# Sheet1_-.net
KiCad netlist of a schematic drawn in Altium Designer
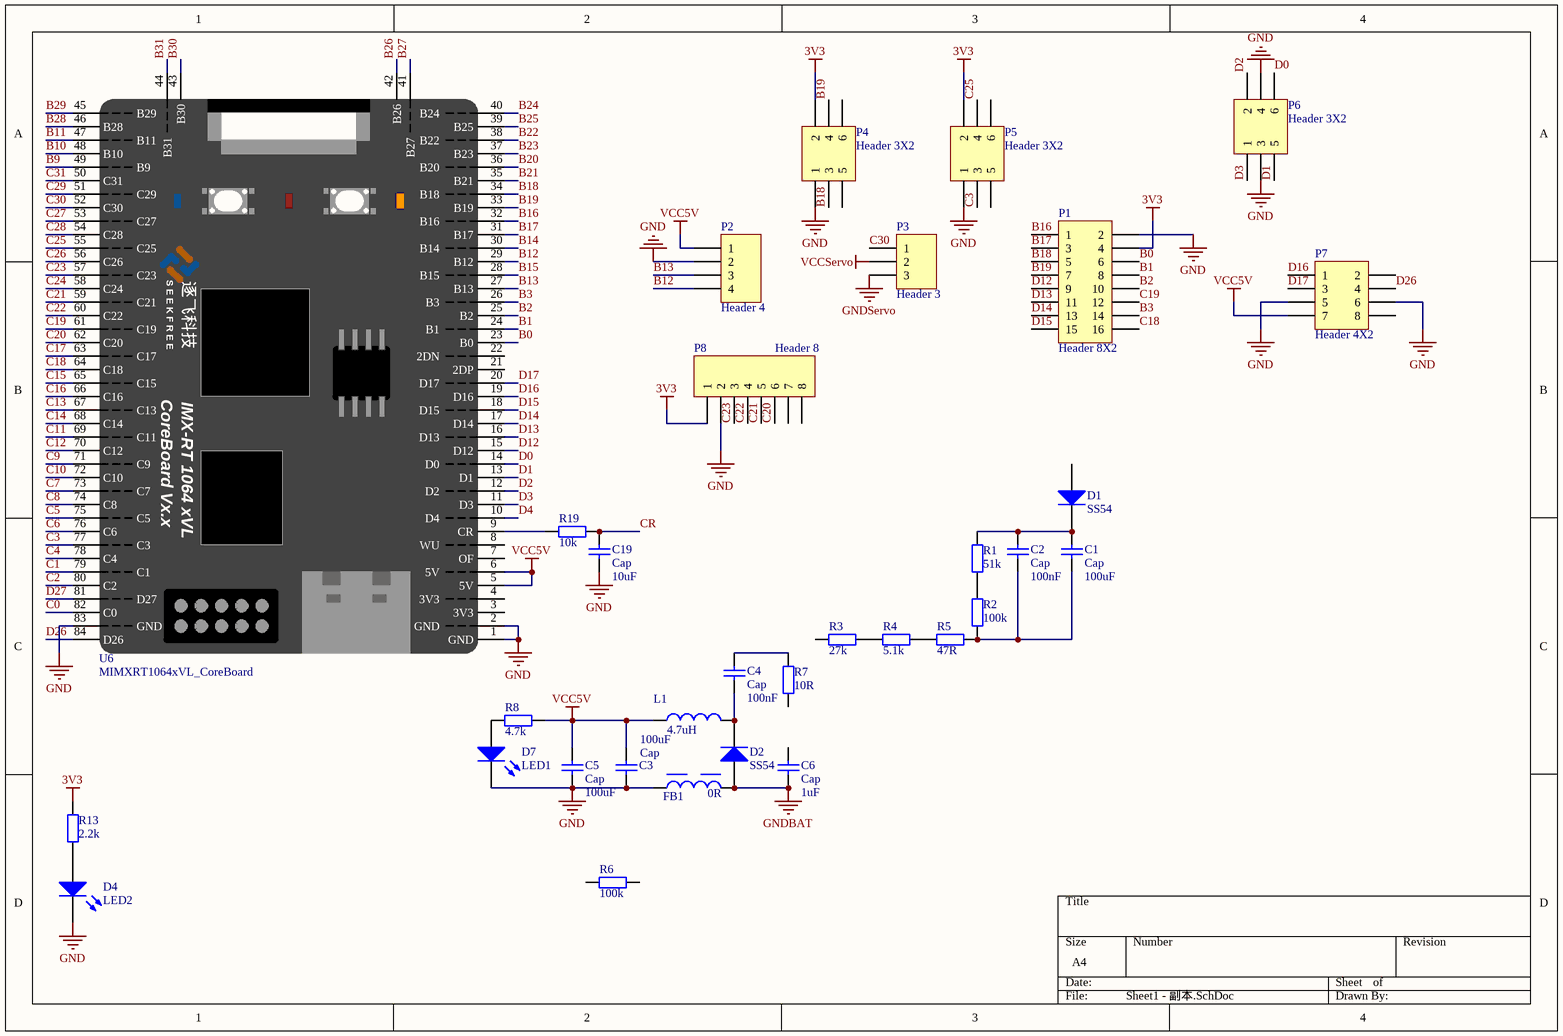
[diagram p0: Sheet1 - 副本.SchDoc]

(export (version "E")
  (design (tool "Eeschema 10.0.6"))
  (components
    (comp (ref "C1")
      (value "Cap")
      (footprint "0603C")
      (description "Capacitor")
      (fields (field (name "ALTIUM_VALUE") "100uF") (field (name "PUBLISHER") "Altium Limited"))
      (libsource (lib "Schlib1") (part "Cap"))
    )
    (comp (ref "C2")
      (value "Cap")
      (footprint "0603C")
      (description "Capacitor")
      (fields (field (name "ALTIUM_VALUE") "100nF") (field (name "PUBLISHER") "Altium Limited"))
      (libsource (lib "Schlib1") (part "Cap"))
    )
    (comp (ref "C3")
      (value "Cap")
      (footprint "0603C")
      (description "Capacitor")
      (fields (field (name "ALTIUM_VALUE") "100uF") (field (name "PUBLISHER") "Altium Limited"))
      (libsource (lib "Schlib1") (part "Cap"))
    )
    (comp (ref "C4")
      (value "Cap")
      (footprint "0603C")
      (description "Capacitor")
      (fields (field (name "ALTIUM_VALUE") "100nF") (field (name "PUBLISHER") "Altium Limited"))
      (libsource (lib "Schlib1") (part "Cap"))
    )
    (comp (ref "C5")
      (value "Cap")
      (footprint "0603C")
      (description "Capacitor")
      (fields (field (name "ALTIUM_VALUE") "100uF") (field (name "PUBLISHER") "Altium Limited"))
      (libsource (lib "Schlib1") (part "Cap"))
    )
    (comp (ref "C6")
      (value "Cap")
      (footprint "0603C")
      (description "Capacitor")
      (fields (field (name "ALTIUM_VALUE") "1uF") (field (name "PUBLISHER") "Altium Limited"))
      (libsource (lib "Schlib1") (part "Cap"))
    )
    (comp (ref "C19")
      (value "Cap")
      (footprint "0603C")
      (description "Capacitor")
      (fields (field (name "ALTIUM_VALUE") "10uF") (field (name "PUBLISHER") "Altium Limited"))
      (libsource (lib "Schlib1") (part "Cap"))
    )
    (comp (ref "D1")
      (value "SS54")
      (footprint "ss54")
      (description "Default Diode")
      (fields (field (name "PUBLISHER") "Altium Limited"))
      (libsource (lib "Schlib1") (part "Diode_1"))
    )
    (comp (ref "D2")
      (value "SS54")
      (footprint "ss54")
      (description "Default Diode")
      (fields (field (name "PUBLISHER") "Altium Limited"))
      (libsource (lib "Schlib1") (part "Diode_1"))
    )
    (comp (ref "D4")
      (value "LED2")
      (footprint "0603C")
      (description "Typical RED, GREEN, YELLOW, AMBER GaAs LED")
      (fields (field (name "PUBLISHER") "Altium Limited"))
      (libsource (lib "Schlib1") (part "LED2"))
    )
    (comp (ref "D7")
      (value "LED1")
      (footprint "0603C")
      (description "Typical RED, GREEN, YELLOW, AMBER GaAs LED")
      (fields (field (name "PUBLISHER") "Altium Limited"))
      (libsource (lib "Schlib1") (part "LED2"))
    )
    (comp (ref "FB1")
      (value "0R")
      (footprint "0805")
      (description "Inductor")
      (fields (field (name "PUBLISHER") "Altium Limited"))
      (libsource (lib "Schlib1") (part "FB"))
    )
    (comp (ref "L1")
      (value "4.7uH")
      (footprint "4R7")
      (description "Inductor")
      (fields (field (name "PUBLISHER") "Altium Limited"))
      (libsource (lib "Schlib1") (part "Inductor_2"))
    )
    (comp (ref "P1")
      (value "Header 8X2")
      (footprint "HDR2X8")
      (description "Header, 8-Pin, Dual row")
      (fields (field (name "PUBLISHER") "Altium Limited"))
      (libsource (lib "Miscellaneous Connectors") (part "Header 8X2"))
    )
    (comp (ref "P2")
      (value "Header 4")
      (footprint "HDR1X4")
      (description "Header, 4-Pin")
      (fields (field (name "PUBLISHER") "Altium Limited"))
      (libsource (lib "Miscellaneous Connectors") (part "Header 4"))
    )
    (comp (ref "P3")
      (value "Header 3")
      (footprint "HDR1X3")
      (description "Header, 3-Pin")
      (fields (field (name "PUBLISHER") "Altium Limited"))
      (libsource (lib "Miscellaneous Connectors") (part "Header 3"))
    )
    (comp (ref "P4")
      (value "Header 3X2")
      (footprint "HDR2X3")
      (description "Header, 3-Pin, Dual row")
      (fields (field (name "PUBLISHER") "Altium Limited"))
      (libsource (lib "Miscellaneous Connectors") (part "Header 3X2"))
    )
    (comp (ref "P5")
      (value "Header 3X2")
      (footprint "HDR2X3")
      (description "Header, 3-Pin, Dual row")
      (fields (field (name "PUBLISHER") "Altium Limited"))
      (libsource (lib "Miscellaneous Connectors") (part "Header 3X2"))
    )
    (comp (ref "P6")
      (value "Header 3X2")
      (footprint "HDR2X3")
      (description "Header, 3-Pin, Dual row")
      (fields (field (name "PUBLISHER") "Altium Limited"))
      (libsource (lib "Miscellaneous Connectors") (part "Header 3X2"))
    )
    (comp (ref "P7")
      (value "Header 4X2")
      (footprint "HDR2X4")
      (description "Header, 4-Pin, Dual row")
      (fields (field (name "PUBLISHER") "Altium Limited"))
      (libsource (lib "Miscellaneous Connectors") (part "Header 4X2"))
    )
    (comp (ref "P8")
      (value "Header 8")
      (footprint "HDR1X8")
      (description "Header, 8-Pin")
      (fields (field (name "PUBLISHER") "Altium Limited"))
      (libsource (lib "Miscellaneous Connectors") (part "Header 8"))
    )
    (comp (ref "R1")
      (value "51k")
      (footprint "0603C")
      (description "Resistor")
      (fields (field (name "Comment") "Res2") (field (name "PUBLISHER") "Altium Limited"))
      (libsource (lib "") (part "Res2_1"))
    )
    (comp (ref "R2")
      (value "100k")
      (footprint "0603C")
      (description "Resistor")
      (fields (field (name "Comment") "Res2") (field (name "PUBLISHER") "Altium Limited"))
      (libsource (lib "") (part "Res2_1"))
    )
    (comp (ref "R3")
      (value "27k")
      (footprint "0603C")
      (description "Resistor")
      (fields (field (name "Comment") "Res2") (field (name "PUBLISHER") "Altium Limited"))
      (libsource (lib "Schlib1") (part "Res2"))
    )
    (comp (ref "R4")
      (value "5.1k")
      (footprint "0603C")
      (description "Resistor")
      (fields (field (name "Comment") "Res2") (field (name "PUBLISHER") "Altium Limited"))
      (libsource (lib "Schlib1") (part "Res2"))
    )
    (comp (ref "R5")
      (value "47R")
      (footprint "0603C")
      (description "Resistor")
      (fields (field (name "Comment") "Res2") (field (name "PUBLISHER") "Altium Limited"))
      (libsource (lib "Schlib1") (part "Res2"))
    )
    (comp (ref "R6")
      (value "100k")
      (footprint "0603C")
      (description "Resistor")
      (fields (field (name "Comment") "Res2") (field (name "PUBLISHER") "Altium Limited"))
      (libsource (lib "Schlib1") (part "Res2"))
    )
    (comp (ref "R7")
      (value "10R")
      (footprint "0603C")
      (description "Resistor")
      (fields (field (name "Comment") "Res2") (field (name "PUBLISHER") "Altium Limited"))
      (libsource (lib "") (part "Res2_1"))
    )
    (comp (ref "R8")
      (value "4.7k")
      (footprint "0603C")
      (description "Resistor")
      (fields (field (name "Comment") "Res2") (field (name "PUBLISHER") "Altium Limited"))
      (libsource (lib "Schlib1") (part "Res2"))
    )
    (comp (ref "R13")
      (value "2.2k")
      (footprint "0603C")
      (description "Resistor")
      (fields (field (name "Comment") "Res2") (field (name "PUBLISHER") "Altium Limited"))
      (libsource (lib "") (part "Res2_1"))
    )
    (comp (ref "R19")
      (value "10k")
      (footprint "0603C")
      (description "Resistor")
      (fields (field (name "Comment") "Res2") (field (name "PUBLISHER") "Altium Limited"))
      (libsource (lib "Schlib1") (part "Res2"))
    )
    (comp (ref "U6")
      (value "MIMXRT1064xVL_CoreBoard")
      (footprint "MIMXRT1064xVL_CoreBoard")
      (description "逐飞科技i.MX RT1064核心板整体原理，可直接使用")
      (libsource (lib "RT1064 V1.2核心板原理库") (part "MIMXRT1064xVL_CoreBoard"))
    )
  )
  (nets
    (net (code "1") (name "/B0") (class "Default")
      (node (ref "P1") (pin "6") (pinfunction "6_6") (pintype "passive"))
      (node (ref "U6") (pin "23") (pinfunction "B0_23") (pintype "passive"))
    )
    (net (code "2") (name "/B1") (class "Default")
      (node (ref "P1") (pin "8") (pinfunction "8_8") (pintype "passive"))
      (node (ref "U6") (pin "24") (pinfunction "B1_24") (pintype "passive"))
    )
    (net (code "3") (name "/B2") (class "Default")
      (node (ref "P1") (pin "10") (pinfunction "10_10") (pintype "passive"))
      (node (ref "U6") (pin "25") (pinfunction "B2_25") (pintype "passive"))
    )
    (net (code "4") (name "/B3") (class "Default")
      (node (ref "P1") (pin "14") (pinfunction "14_14") (pintype "passive"))
      (node (ref "U6") (pin "26") (pinfunction "B3_26") (pintype "passive"))
    )
    (net (code "5") (name "/B9") (class "Default")
      (node (ref "U6") (pin "49") (pinfunction "B9_49") (pintype "passive"))
    )
    (net (code "6") (name "/B10") (class "Default")
      (node (ref "U6") (pin "48") (pinfunction "B10_48") (pintype "passive"))
    )
    (net (code "7") (name "/B11") (class "Default")
      (node (ref "U6") (pin "47") (pinfunction "B11_47") (pintype "passive"))
    )
    (net (code "8") (name "/B12") (class "Default")
      (node (ref "P2") (pin "4") (pinfunction "4_4") (pintype "passive"))
      (node (ref "U6") (pin "29") (pinfunction "B12_29") (pintype "passive"))
    )
    (net (code "9") (name "/B13") (class "Default")
      (node (ref "P2") (pin "3") (pinfunction "3_3") (pintype "passive"))
      (node (ref "U6") (pin "27") (pinfunction "B13_27") (pintype "passive"))
    )
    (net (code "10") (name "/B14") (class "Default")
      (node (ref "U6") (pin "30") (pinfunction "B14_30") (pintype "passive"))
    )
    (net (code "11") (name "/B15") (class "Default")
      (node (ref "U6") (pin "28") (pinfunction "B15_28") (pintype "passive"))
    )
    (net (code "12") (name "/B16") (class "Default")
      (node (ref "P1") (pin "1") (pinfunction "1_1") (pintype "passive"))
      (node (ref "U6") (pin "32") (pinfunction "B16_32") (pintype "passive"))
    )
    (net (code "13") (name "/B17") (class "Default")
      (node (ref "P1") (pin "3") (pinfunction "3_3") (pintype "passive"))
      (node (ref "U6") (pin "31") (pinfunction "B17_31") (pintype "passive"))
    )
    (net (code "14") (name "/B18") (class "Default")
      (node (ref "P1") (pin "5") (pinfunction "5_5") (pintype "passive"))
      (node (ref "P4") (pin "3") (pinfunction "3_3") (pintype "passive"))
      (node (ref "U6") (pin "34") (pinfunction "B18_34") (pintype "passive"))
    )
    (net (code "15") (name "/B19") (class "Default")
      (node (ref "P1") (pin "7") (pinfunction "7_7") (pintype "passive"))
      (node (ref "P4") (pin "4") (pinfunction "4_4") (pintype "passive"))
      (node (ref "U6") (pin "33") (pinfunction "B19_33") (pintype "passive"))
    )
    (net (code "16") (name "/B20") (class "Default")
      (node (ref "U6") (pin "36") (pinfunction "B20_36") (pintype "passive"))
    )
    (net (code "17") (name "/B21") (class "Default")
      (node (ref "U6") (pin "35") (pinfunction "B21_35") (pintype "passive"))
    )
    (net (code "18") (name "/B22") (class "Default")
      (node (ref "U6") (pin "38") (pinfunction "B22_38") (pintype "passive"))
    )
    (net (code "19") (name "/B23") (class "Default")
      (node (ref "U6") (pin "37") (pinfunction "B23_37") (pintype "passive"))
    )
    (net (code "20") (name "/B24") (class "Default")
      (node (ref "U6") (pin "40") (pinfunction "B24_40") (pintype "passive"))
    )
    (net (code "21") (name "/B25") (class "Default")
      (node (ref "U6") (pin "39") (pinfunction "B25_39") (pintype "passive"))
    )
    (net (code "22") (name "/B26") (class "Default")
      (node (ref "U6") (pin "42") (pinfunction "B26_42") (pintype "passive"))
    )
    (net (code "23") (name "/B27") (class "Default")
      (node (ref "U6") (pin "41") (pinfunction "B27_41") (pintype "passive"))
    )
    (net (code "24") (name "/B28") (class "Default")
      (node (ref "U6") (pin "46") (pinfunction "B28_46") (pintype "passive"))
    )
    (net (code "25") (name "/B29") (class "Default")
      (node (ref "U6") (pin "45") (pinfunction "B29_45") (pintype "passive"))
    )
    (net (code "26") (name "/B30") (class "Default")
      (node (ref "U6") (pin "43") (pinfunction "B30_43") (pintype "passive"))
    )
    (net (code "27") (name "/B31") (class "Default")
      (node (ref "U6") (pin "44") (pinfunction "B31_44") (pintype "passive"))
    )
    (net (code "28") (name "/C0") (class "Default")
      (node (ref "U6") (pin "82") (pinfunction "C0_82") (pintype "passive"))
    )
    (net (code "29") (name "/C1") (class "Default")
      (node (ref "U6") (pin "79") (pinfunction "C1_79") (pintype "passive"))
    )
    (net (code "30") (name "/C2") (class "Default")
      (node (ref "U6") (pin "80") (pinfunction "C2_80") (pintype "passive"))
    )
    (net (code "31") (name "/C3") (class "Default")
      (node (ref "P5") (pin "3") (pinfunction "3_3") (pintype "passive"))
      (node (ref "U6") (pin "77") (pinfunction "C3_77") (pintype "passive"))
    )
    (net (code "32") (name "/C4") (class "Default")
      (node (ref "U6") (pin "78") (pinfunction "C4_78") (pintype "passive"))
    )
    (net (code "33") (name "/C5") (class "Default")
      (node (ref "U6") (pin "75") (pinfunction "C5_75") (pintype "passive"))
    )
    (net (code "34") (name "/C6") (class "Default")
      (node (ref "U6") (pin "76") (pinfunction "C6_76") (pintype "passive"))
    )
    (net (code "35") (name "/C7") (class "Default")
      (node (ref "U6") (pin "73") (pinfunction "C7_73") (pintype "passive"))
    )
    (net (code "36") (name "/C8") (class "Default")
      (node (ref "U6") (pin "74") (pinfunction "C8_74") (pintype "passive"))
    )
    (net (code "37") (name "/C9") (class "Default")
      (node (ref "U6") (pin "71") (pinfunction "C9_71") (pintype "passive"))
    )
    (net (code "38") (name "/C10") (class "Default")
      (node (ref "U6") (pin "72") (pinfunction "C10_72") (pintype "passive"))
    )
    (net (code "39") (name "/C11") (class "Default")
      (node (ref "U6") (pin "69") (pinfunction "C11_69") (pintype "passive"))
    )
    (net (code "40") (name "/C12") (class "Default")
      (node (ref "U6") (pin "70") (pinfunction "C12_70") (pintype "passive"))
    )
    (net (code "41") (name "/C13") (class "Default")
      (node (ref "U6") (pin "67") (pinfunction "C13_67") (pintype "passive"))
    )
    (net (code "42") (name "/C14") (class "Default")
      (node (ref "U6") (pin "68") (pinfunction "C14_68") (pintype "passive"))
    )
    (net (code "43") (name "/C15") (class "Default")
      (node (ref "U6") (pin "65") (pinfunction "C15_65") (pintype "passive"))
    )
    (net (code "44") (name "/C16") (class "Default")
      (node (ref "U6") (pin "66") (pinfunction "C16_66") (pintype "passive"))
    )
    (net (code "45") (name "/C17") (class "Default")
      (node (ref "U6") (pin "63") (pinfunction "C17_63") (pintype "passive"))
    )
    (net (code "46") (name "/C18") (class "Default")
      (node (ref "P1") (pin "16") (pinfunction "16_16") (pintype "passive"))
      (node (ref "U6") (pin "64") (pinfunction "C18_64") (pintype "passive"))
    )
    (net (code "47") (name "/C19") (class "Default")
      (node (ref "P1") (pin "12") (pinfunction "12_12") (pintype "passive"))
      (node (ref "U6") (pin "61") (pinfunction "C19_61") (pintype "passive"))
    )
    (net (code "48") (name "/C20") (class "Default")
      (node (ref "P8") (pin "6") (pinfunction "6_6") (pintype "passive"))
      (node (ref "U6") (pin "62") (pinfunction "C20_62") (pintype "passive"))
    )
    (net (code "49") (name "/C21") (class "Default")
      (node (ref "P8") (pin "5") (pinfunction "5_5") (pintype "passive"))
      (node (ref "U6") (pin "59") (pinfunction "C21_59") (pintype "passive"))
    )
    (net (code "50") (name "/C22") (class "Default")
      (node (ref "P8") (pin "4") (pinfunction "4_4") (pintype "passive"))
      (node (ref "U6") (pin "60") (pinfunction "C22_60") (pintype "passive"))
    )
    (net (code "51") (name "/C23") (class "Default")
      (node (ref "P8") (pin "3") (pinfunction "3_3") (pintype "passive"))
      (node (ref "U6") (pin "57") (pinfunction "C23_57") (pintype "passive"))
    )
    (net (code "52") (name "/C24") (class "Default")
      (node (ref "U6") (pin "58") (pinfunction "C24_58") (pintype "passive"))
    )
    (net (code "53") (name "/C25") (class "Default")
      (node (ref "P5") (pin "4") (pinfunction "4_4") (pintype "passive"))
      (node (ref "U6") (pin "55") (pinfunction "C25_55") (pintype "passive"))
    )
    (net (code "54") (name "/C26") (class "Default")
      (node (ref "U6") (pin "56") (pinfunction "C26_56") (pintype "passive"))
    )
    (net (code "55") (name "/C27") (class "Default")
      (node (ref "U6") (pin "53") (pinfunction "C27_53") (pintype "passive"))
    )
    (net (code "56") (name "/C28") (class "Default")
      (node (ref "U6") (pin "54") (pinfunction "C28_54") (pintype "passive"))
    )
    (net (code "57") (name "/C29") (class "Default")
      (node (ref "U6") (pin "51") (pinfunction "C29_51") (pintype "passive"))
    )
    (net (code "58") (name "/C30") (class "Default")
      (node (ref "P3") (pin "1") (pinfunction "1_1") (pintype "passive"))
      (node (ref "U6") (pin "52") (pinfunction "C30_52") (pintype "passive"))
    )
    (net (code "59") (name "/C31") (class "Default")
      (node (ref "U6") (pin "50") (pinfunction "C31_50") (pintype "passive"))
    )
    (net (code "60") (name "/CR") (class "Default")
      (node (ref "C19") (pin "2") (pinfunction "2_2") (pintype "passive"))
      (node (ref "R19") (pin "2") (pinfunction "2_2") (pintype "passive"))
    )
    (net (code "61") (name "/D0") (class "Default")
      (node (ref "P6") (pin "6") (pinfunction "6_6") (pintype "passive"))
      (node (ref "U6") (pin "14") (pinfunction "D0_14") (pintype "passive"))
    )
    (net (code "62") (name "/D1") (class "Default")
      (node (ref "P6") (pin "5") (pinfunction "5_5") (pintype "passive"))
      (node (ref "U6") (pin "13") (pinfunction "D1_13") (pintype "passive"))
    )
    (net (code "63") (name "/D2") (class "Default")
      (node (ref "P6") (pin "2") (pinfunction "2_2") (pintype "passive"))
      (node (ref "U6") (pin "12") (pinfunction "D2_12") (pintype "passive"))
    )
    (net (code "64") (name "/D3") (class "Default")
      (node (ref "P6") (pin "1") (pinfunction "1_1") (pintype "passive"))
      (node (ref "U6") (pin "11") (pinfunction "D3_11") (pintype "passive"))
    )
    (net (code "65") (name "/D4") (class "Default")
      (node (ref "U6") (pin "10") (pinfunction "D4_10") (pintype "passive"))
    )
    (net (code "66") (name "/D12") (class "Default")
      (node (ref "P1") (pin "9") (pinfunction "9_9") (pintype "passive"))
      (node (ref "U6") (pin "15") (pinfunction "D12_15") (pintype "passive"))
    )
    (net (code "67") (name "/D13") (class "Default")
      (node (ref "P1") (pin "11") (pinfunction "11_11") (pintype "passive"))
      (node (ref "U6") (pin "16") (pinfunction "D13_16") (pintype "passive"))
    )
    (net (code "68") (name "/D14") (class "Default")
      (node (ref "P1") (pin "13") (pinfunction "13_13") (pintype "passive"))
      (node (ref "U6") (pin "17") (pinfunction "D14_17") (pintype "passive"))
    )
    (net (code "69") (name "/D15") (class "Default")
      (node (ref "P1") (pin "15") (pinfunction "15_15") (pintype "passive"))
      (node (ref "U6") (pin "18") (pinfunction "D15_18") (pintype "passive"))
    )
    (net (code "70") (name "/D16") (class "Default")
      (node (ref "P7") (pin "1") (pinfunction "1_1") (pintype "passive"))
      (node (ref "U6") (pin "19") (pinfunction "D16_19") (pintype "passive"))
    )
    (net (code "71") (name "/D17") (class "Default")
      (node (ref "P7") (pin "3") (pinfunction "3_3") (pintype "passive"))
      (node (ref "U6") (pin "20") (pinfunction "D17_20") (pintype "passive"))
    )
    (net (code "72") (name "/D26") (class "Default")
      (node (ref "P7") (pin "4") (pinfunction "4_4") (pintype "passive"))
      (node (ref "U6") (pin "84") (pinfunction "D26_84") (pintype "passive"))
    )
    (net (code "73") (name "/D27") (class "Default")
      (node (ref "U6") (pin "81") (pinfunction "D27_81") (pintype "passive"))
    )
    (net (code "74") (name "3V3") (class "Default")
      (node (ref "P1") (pin "4") (pinfunction "4_4") (pintype "passive"))
      (node (ref "P4") (pin "2") (pinfunction "2_2") (pintype "passive"))
      (node (ref "P5") (pin "2") (pinfunction "2_2") (pintype "passive"))
      (node (ref "P8") (pin "1") (pinfunction "1_1") (pintype "passive"))
      (node (ref "R13") (pin "2") (pinfunction "2_2") (pintype "passive"))
    )
    (net (code "75") (name "GND") (class "Default")
      (node (ref "C19") (pin "1") (pinfunction "1_1") (pintype "passive"))
      (node (ref "C3") (pin "1") (pinfunction "1_1") (pintype "passive"))
      (node (ref "C5") (pin "1") (pinfunction "1_1") (pintype "passive"))
      (node (ref "D4") (pin "2") (pinfunction "K_2") (pintype "passive"))
      (node (ref "D7") (pin "2") (pinfunction "K_2") (pintype "passive"))
      (node (ref "FB1") (pin "1") (pinfunction "1_1") (pintype "passive"))
      (node (ref "P1") (pin "2") (pinfunction "2_2") (pintype "passive"))
      (node (ref "P2") (pin "2") (pinfunction "2_2") (pintype "passive"))
      (node (ref "P4") (pin "1") (pinfunction "1_1") (pintype "passive"))
      (node (ref "P5") (pin "1") (pinfunction "1_1") (pintype "passive"))
      (node (ref "P6") (pin "3") (pinfunction "3_3") (pintype "passive"))
      (node (ref "P6") (pin "4") (pinfunction "4_4") (pintype "passive"))
      (node (ref "P7") (pin "5") (pinfunction "5_5") (pintype "passive"))
      (node (ref "P7") (pin "6") (pinfunction "6_6") (pintype "passive"))
      (node (ref "P8") (pin "2") (pinfunction "2_2") (pintype "passive"))
      (node (ref "U6") (pin "1") (pinfunction "GND_1") (pintype "passive"))
      (node (ref "U6") (pin "2") (pinfunction "GND_2") (pintype "passive"))
      (node (ref "U6") (pin "83") (pinfunction "GND_83") (pintype "passive"))
    )
    (net (code "76") (name "GNDBAT") (class "Default")
      (node (ref "C6") (pin "1") (pinfunction "1_1") (pintype "passive"))
      (node (ref "D2") (pin "1") (pinfunction "A_1") (pintype "passive"))
      (node (ref "FB1") (pin "2") (pinfunction "2_2") (pintype "passive"))
    )
    (net (code "77") (name "GNDServo") (class "Default")
      (node (ref "P3") (pin "3") (pinfunction "3_3") (pintype "passive"))
    )
    (net (code "78") (name "Net-(C1-Pad1)") (class "Default")
      (node (ref "C1") (pin "1") (pinfunction "1_1") (pintype "passive"))
      (node (ref "C2") (pin "1") (pinfunction "1_1") (pintype "passive"))
      (node (ref "R2") (pin "1") (pinfunction "1_1") (pintype "passive"))
      (node (ref "R5") (pin "2") (pinfunction "2_2") (pintype "passive"))
    )
    (net (code "79") (name "Net-(C4-Pad2)") (class "Default")
      (node (ref "C4") (pin "2") (pinfunction "2_2") (pintype "passive"))
      (node (ref "R7") (pin "2") (pinfunction "2_2") (pintype "passive"))
    )
    (net (code "80") (name "Net-(D1-K)") (class "Default")
      (node (ref "C1") (pin "2") (pinfunction "2_2") (pintype "passive"))
      (node (ref "C2") (pin "2") (pinfunction "2_2") (pintype "passive"))
      (node (ref "D1") (pin "2") (pinfunction "K_2") (pintype "passive"))
      (node (ref "R1") (pin "2") (pinfunction "2_2") (pintype "passive"))
    )
    (net (code "81") (name "Net-(D2-K)") (class "Default")
      (node (ref "C4") (pin "1") (pinfunction "1_1") (pintype "passive"))
      (node (ref "D2") (pin "2") (pinfunction "K_2") (pintype "passive"))
      (node (ref "L1") (pin "2") (pinfunction "2_2") (pintype "passive"))
    )
    (net (code "82") (name "Net-(D4-A)") (class "Default")
      (node (ref "D4") (pin "1") (pinfunction "A_1") (pintype "passive"))
      (node (ref "R13") (pin "1") (pinfunction "1_1") (pintype "passive"))
    )
    (net (code "83") (name "Net-(D7-A)") (class "Default")
      (node (ref "D7") (pin "1") (pinfunction "A_1") (pintype "passive"))
      (node (ref "R8") (pin "1") (pinfunction "1_1") (pintype "passive"))
    )
    (net (code "84") (name "Net-(R1-Pad1)") (class "Default")
      (node (ref "R1") (pin "1") (pinfunction "1_1") (pintype "passive"))
      (node (ref "R2") (pin "2") (pinfunction "2_2") (pintype "passive"))
    )
    (net (code "85") (name "Net-(R3-Pad2)") (class "Default")
      (node (ref "R3") (pin "2") (pinfunction "2_2") (pintype "passive"))
      (node (ref "R4") (pin "1") (pinfunction "1_1") (pintype "passive"))
    )
    (net (code "86") (name "Net-(R4-Pad2)") (class "Default")
      (node (ref "R4") (pin "2") (pinfunction "2_2") (pintype "passive"))
      (node (ref "R5") (pin "1") (pinfunction "1_1") (pintype "passive"))
    )
    (net (code "87") (name "Net-(U6-CR)") (class "Default")
      (node (ref "R19") (pin "1") (pinfunction "1_1") (pintype "passive"))
      (node (ref "U6") (pin "9") (pinfunction "CR_9") (pintype "passive"))
    )
    (net (code "88") (name "VCC5V") (class "Default")
      (node (ref "C3") (pin "2") (pinfunction "2_2") (pintype "passive"))
      (node (ref "C5") (pin "2") (pinfunction "2_2") (pintype "passive"))
      (node (ref "L1") (pin "1") (pinfunction "1_1") (pintype "passive"))
      (node (ref "P2") (pin "1") (pinfunction "1_1") (pintype "passive"))
      (node (ref "P7") (pin "7") (pinfunction "7_7") (pintype "passive"))
      (node (ref "R8") (pin "2") (pinfunction "2_2") (pintype "passive"))
      (node (ref "U6") (pin "5") (pinfunction "5V_5") (pintype "passive"))
      (node (ref "U6") (pin "6") (pinfunction "5V_6") (pintype "passive"))
    )
    (net (code "89") (name "VCCServo") (class "Default")
      (node (ref "P3") (pin "2") (pinfunction "2_2") (pintype "passive"))
    )
    (net (code "90") (name "unconnected-(C6-Pad2)") (class "Default")
      (node (ref "C6") (pin "2") (pinfunction "2_2") (pintype "passive"))
    )
    (net (code "91") (name "unconnected-(D1-A-Pad1)") (class "Default")
      (node (ref "D1") (pin "1") (pinfunction "A_1") (pintype "passive"))
    )
    (net (code "92") (name "unconnected-(P4-Pad5)") (class "Default")
      (node (ref "P4") (pin "5") (pinfunction "5_5") (pintype "passive"))
    )
    (net (code "93") (name "unconnected-(P4-Pad6)") (class "Default")
      (node (ref "P4") (pin "6") (pinfunction "6_6") (pintype "passive"))
    )
    (net (code "94") (name "unconnected-(P5-Pad5)") (class "Default")
      (node (ref "P5") (pin "5") (pinfunction "5_5") (pintype "passive"))
    )
    (net (code "95") (name "unconnected-(P5-Pad6)") (class "Default")
      (node (ref "P5") (pin "6") (pinfunction "6_6") (pintype "passive"))
    )
    (net (code "96") (name "unconnected-(P7-Pad2)") (class "Default")
      (node (ref "P7") (pin "2") (pinfunction "2_2") (pintype "passive"))
    )
    (net (code "97") (name "unconnected-(P7-Pad8)") (class "Default")
      (node (ref "P7") (pin "8") (pinfunction "8_8") (pintype "passive"))
    )
    (net (code "98") (name "unconnected-(P8-Pad7)") (class "Default")
      (node (ref "P8") (pin "7") (pinfunction "7_7") (pintype "passive"))
    )
    (net (code "99") (name "unconnected-(P8-Pad8)") (class "Default")
      (node (ref "P8") (pin "8") (pinfunction "8_8") (pintype "passive"))
    )
    (net (code "100") (name "unconnected-(R3-Pad1)") (class "Default")
      (node (ref "R3") (pin "1") (pinfunction "1_1") (pintype "passive"))
    )
    (net (code "101") (name "unconnected-(R6-Pad1)") (class "Default")
      (node (ref "R6") (pin "1") (pinfunction "1_1") (pintype "passive"))
    )
    (net (code "102") (name "unconnected-(R6-Pad2)") (class "Default")
      (node (ref "R6") (pin "2") (pinfunction "2_2") (pintype "passive"))
    )
    (net (code "103") (name "unconnected-(R7-Pad1)") (class "Default")
      (node (ref "R7") (pin "1") (pinfunction "1_1") (pintype "passive"))
    )
    (net (code "104") (name "unconnected-(U6-2DN-Pad22)") (class "Default")
      (node (ref "U6") (pin "22") (pinfunction "2DN_22") (pintype "passive"))
    )
    (net (code "105") (name "unconnected-(U6-2DP-Pad21)") (class "Default")
      (node (ref "U6") (pin "21") (pinfunction "2DP_21") (pintype "passive"))
    )
    (net (code "106") (name "unconnected-(U6-3V3-Pad3)") (class "Default")
      (node (ref "U6") (pin "3") (pinfunction "3V3_3") (pintype "passive"))
    )
    (net (code "107") (name "unconnected-(U6-3V3-Pad4)") (class "Default")
      (node (ref "U6") (pin "4") (pinfunction "3V3_4") (pintype "passive"))
    )
    (net (code "108") (name "unconnected-(U6-OF-Pad7)") (class "Default")
      (node (ref "U6") (pin "7") (pinfunction "OF_7") (pintype "passive"))
    )
    (net (code "109") (name "unconnected-(U6-WU-Pad8)") (class "Default")
      (node (ref "U6") (pin "8") (pinfunction "WU_8") (pintype "passive"))
    )
  )
)
